# audio.net
KiCad netlist of a schematic drawn in Altium Designer
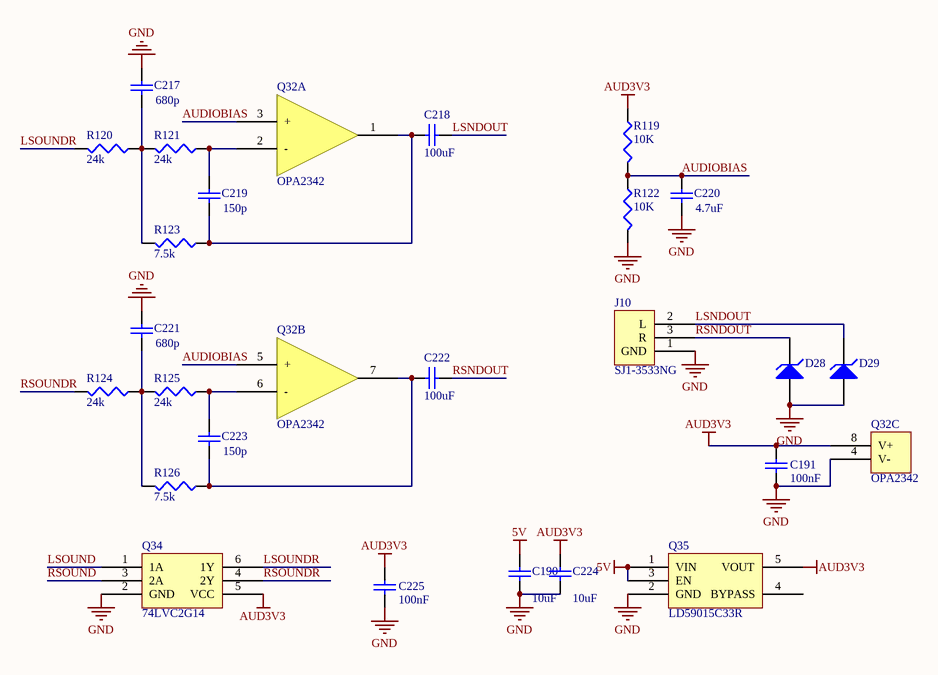
[diagram p0: audio.SchDoc]

(export (version "E")
  (design (tool "Eeschema 10.0.6"))
  (components
    (comp (ref "C190")
      (value "10uF")
      (footprint "CAPC1608X90N")
      (description "Capacitor")
      (fields (field (name "Comment") "GRM188R60G106ME47") (field (name "PUBLISHER") "Altium Limited"))
      (libsource (lib "Miscellaneous Devices") (part "Cap"))
    )
    (comp (ref "C191")
      (value "100nF")
      (footprint "CAPC1005X06L")
      (description "Capacitor")
      (fields (field (name "Comment") "Cap") (field (name "PUBLISHER") "Altium Limited"))
      (libsource (lib "Miscellaneous Devices") (part "Cap"))
    )
    (comp (ref "C217")
      (value "680p")
      (footprint "CAPC1608X90N")
      (description "Capacitor")
      (fields (field (name "PUBLISHER") "Altium Limited"))
      (libsource (lib "Miscellaneous Devices") (part "Cap"))
    )
    (comp (ref "C218")
      (value "100uF")
      (footprint "CAPC3225X220N")
      (description "Capacitor")
      (fields (field (name "Comment") "GRM31CR60J107ME39L") (field (name "PUBLISHER") "Altium Limited"))
      (libsource (lib "Miscellaneous Devices") (part "Cap"))
    )
    (comp (ref "C219")
      (value "150p")
      (footprint "CAPC1608X90N")
      (description "Capacitor")
      (fields (field (name "PUBLISHER") "Altium Limited"))
      (libsource (lib "Miscellaneous Devices") (part "Cap"))
    )
    (comp (ref "C220")
      (value "4.7uF")
      (footprint "CAPC1608X90N")
      (description "Capacitor")
      (fields (field (name "Comment") "GRM188R60J475ME19D") (field (name "PUBLISHER") "Altium Limited"))
      (libsource (lib "Miscellaneous Devices") (part "Cap"))
    )
    (comp (ref "C221")
      (value "680p")
      (footprint "CAPC1608X90N")
      (description "Capacitor")
      (fields (field (name "PUBLISHER") "Altium Limited"))
      (libsource (lib "Miscellaneous Devices") (part "Cap"))
    )
    (comp (ref "C222")
      (value "100uF")
      (footprint "CAPC3225X220N")
      (description "Capacitor")
      (fields (field (name "Comment") "GRM31CR60J107ME39L") (field (name "PUBLISHER") "Altium Limited"))
      (libsource (lib "Miscellaneous Devices") (part "Cap"))
    )
    (comp (ref "C223")
      (value "150p")
      (footprint "CAPC1608X90N")
      (description "Capacitor")
      (fields (field (name "PUBLISHER") "Altium Limited"))
      (libsource (lib "Miscellaneous Devices") (part "Cap"))
    )
    (comp (ref "C224")
      (value "10uF")
      (footprint "CAPC1608X90N")
      (description "Capacitor")
      (fields (field (name "Comment") "GRM188R60G106ME47") (field (name "PUBLISHER") "Altium Limited"))
      (libsource (lib "Miscellaneous Devices") (part "Cap"))
    )
    (comp (ref "C225")
      (value "100nF")
      (footprint "CAPC1005X06L")
      (description "Capacitor")
      (fields (field (name "Comment") "Cap") (field (name "PUBLISHER") "Altium Limited"))
      (libsource (lib "Miscellaneous Devices") (part "Cap"))
    )
    (comp (ref "D28")
      (value "EZAEG2A")
      (footprint "CAPC1005X55N")
      (description "Zener Diode")
      (fields (field (name "PUBLISHER") "Altium Limited"))
      (libsource (lib "Miscellaneous Devices") (part "D Zener"))
    )
    (comp (ref "D29")
      (value "EZAEG2A")
      (footprint "CAPC1005X55N")
      (description "Zener Diode")
      (fields (field (name "PUBLISHER") "Altium Limited"))
      (libsource (lib "Miscellaneous Devices") (part "D Zener"))
    )
    (comp (ref "J10") (value "SJ1-3533NG") (footprint "SJ1-3533NG") (libsource (lib "schlib") (part "AUDIO")))
    (comp (ref "Q32")
      (value "OPA2342")
      (footprint "SOIC127P600X175-8AN")
      (libsource (lib "schlib") (part "OPAMP"))
    )
    (comp (ref "Q34")
      (value "74LVC2G14")
      (footprint "74LVC2G14-SOP6")
      (libsource (lib "schlib") (part "74LVC2G14"))
    )
    (comp (ref "Q35") (value "LD59015C33R") (footprint "SOT23-5") (libsource (lib "schlib") (part "LDO")))
    (comp (ref "R119")
      (value "10K")
      (footprint "J1-0603")
      (description "Resistor")
      (fields (field (name "Comment") "RC1608F103CS") (field (name "PUBLISHER") "Altium Limited"))
      (libsource (lib "Miscellaneous Devices") (part "Res3"))
    )
    (comp (ref "R120")
      (value "24k")
      (footprint "J1-0603")
      (description "Resistor")
      (fields (field (name "Comment") "RC1608F471CS") (field (name "PUBLISHER") "Altium Limited"))
      (libsource (lib "Miscellaneous Devices") (part "Res3"))
    )
    (comp (ref "R121")
      (value "24k")
      (footprint "J1-0603")
      (description "Resistor")
      (fields (field (name "Comment") "RC1608F471CS") (field (name "PUBLISHER") "Altium Limited"))
      (libsource (lib "Miscellaneous Devices") (part "Res3"))
    )
    (comp (ref "R122")
      (value "10K")
      (footprint "J1-0603")
      (description "Resistor")
      (fields (field (name "Comment") "RC1608F103CS") (field (name "PUBLISHER") "Altium Limited"))
      (libsource (lib "Miscellaneous Devices") (part "Res3"))
    )
    (comp (ref "R123")
      (value "7.5k")
      (footprint "J1-0603")
      (description "Resistor")
      (fields (field (name "Comment") "RC1608F471CS") (field (name "PUBLISHER") "Altium Limited"))
      (libsource (lib "Miscellaneous Devices") (part "Res3"))
    )
    (comp (ref "R124")
      (value "24k")
      (footprint "J1-0603")
      (description "Resistor")
      (fields (field (name "Comment") "RC1608F471CS") (field (name "PUBLISHER") "Altium Limited"))
      (libsource (lib "Miscellaneous Devices") (part "Res3"))
    )
    (comp (ref "R125")
      (value "24k")
      (footprint "J1-0603")
      (description "Resistor")
      (fields (field (name "Comment") "RC1608F471CS") (field (name "PUBLISHER") "Altium Limited"))
      (libsource (lib "Miscellaneous Devices") (part "Res3"))
    )
    (comp (ref "R126")
      (value "7.5k")
      (footprint "J1-0603")
      (description "Resistor")
      (fields (field (name "Comment") "RC1608F471CS") (field (name "PUBLISHER") "Altium Limited"))
      (libsource (lib "Miscellaneous Devices") (part "Res3"))
    )
  )
  (nets
    (net (code "1") (name "/AUDIOBIAS") (class "Default")
      (node (ref "C220") (pin "2") (pinfunction "2_2") (pintype "passive"))
      (node (ref "Q32") (pin "3") (pinfunction "+_3") (pintype "passive"))
      (node (ref "Q32") (pin "5") (pinfunction "+_5") (pintype "passive"))
      (node (ref "R119") (pin "2") (pinfunction "2_2") (pintype "passive"))
      (node (ref "R122") (pin "1") (pinfunction "1_1") (pintype "passive"))
    )
    (net (code "2") (name "/LSNDOUT") (class "Default")
      (node (ref "C218") (pin "2") (pinfunction "2_2") (pintype "passive"))
      (node (ref "D29") (pin "2") (pinfunction "K_2") (pintype "passive"))
      (node (ref "J10") (pin "2") (pinfunction "L_2") (pintype "passive"))
    )
    (net (code "3") (name "/LSOUND") (class "Default")
      (node (ref "Q34") (pin "1") (pinfunction "1A_1") (pintype "passive"))
    )
    (net (code "4") (name "/LSOUNDR") (class "Default")
      (node (ref "Q34") (pin "6") (pinfunction "1Y_6") (pintype "passive"))
      (node (ref "R120") (pin "2") (pinfunction "2_2") (pintype "passive"))
    )
    (net (code "5") (name "/RSNDOUT") (class "Default")
      (node (ref "C222") (pin "2") (pinfunction "2_2") (pintype "passive"))
      (node (ref "D28") (pin "2") (pinfunction "K_2") (pintype "passive"))
      (node (ref "J10") (pin "3") (pinfunction "R_3") (pintype "passive"))
    )
    (net (code "6") (name "/RSOUND") (class "Default")
      (node (ref "Q34") (pin "3") (pinfunction "2A_3") (pintype "passive"))
    )
    (net (code "7") (name "/RSOUNDR") (class "Default")
      (node (ref "Q34") (pin "4") (pinfunction "2Y_4") (pintype "passive"))
      (node (ref "R124") (pin "2") (pinfunction "2_2") (pintype "passive"))
    )
    (net (code "8") (name "5V") (class "Default")
      (node (ref "C190") (pin "2") (pinfunction "2_2") (pintype "passive"))
      (node (ref "Q35") (pin "1") (pinfunction "VIN_1") (pintype "passive"))
      (node (ref "Q35") (pin "3") (pinfunction "EN_3") (pintype "passive"))
    )
    (net (code "9") (name "AUD3V3") (class "Default")
      (node (ref "C191") (pin "2") (pinfunction "2_2") (pintype "passive"))
      (node (ref "C224") (pin "2") (pinfunction "2_2") (pintype "passive"))
      (node (ref "C225") (pin "2") (pinfunction "2_2") (pintype "passive"))
      (node (ref "Q32") (pin "8") (pinfunction "V+_8") (pintype "passive"))
      (node (ref "Q34") (pin "5") (pinfunction "VCC_5") (pintype "passive"))
      (node (ref "Q35") (pin "5") (pinfunction "VOUT_5") (pintype "passive"))
      (node (ref "R119") (pin "1") (pinfunction "1_1") (pintype "passive"))
    )
    (net (code "10") (name "GND") (class "Default")
      (node (ref "C190") (pin "1") (pinfunction "1_1") (pintype "passive"))
      (node (ref "C191") (pin "1") (pinfunction "1_1") (pintype "passive"))
      (node (ref "C217") (pin "2") (pinfunction "2_2") (pintype "passive"))
      (node (ref "C220") (pin "1") (pinfunction "1_1") (pintype "passive"))
      (node (ref "C221") (pin "2") (pinfunction "2_2") (pintype "passive"))
      (node (ref "C224") (pin "1") (pinfunction "1_1") (pintype "passive"))
      (node (ref "C225") (pin "1") (pinfunction "1_1") (pintype "passive"))
      (node (ref "D28") (pin "1") (pinfunction "A_1") (pintype "passive"))
      (node (ref "D29") (pin "1") (pinfunction "A_1") (pintype "passive"))
      (node (ref "J10") (pin "1") (pinfunction "GND_1") (pintype "passive"))
      (node (ref "Q32") (pin "4") (pinfunction "V-_4") (pintype "passive"))
      (node (ref "Q34") (pin "2") (pinfunction "GND_2") (pintype "passive"))
      (node (ref "Q35") (pin "2") (pinfunction "GND_2") (pintype "passive"))
      (node (ref "R122") (pin "2") (pinfunction "2_2") (pintype "passive"))
    )
    (net (code "11") (name "Net-(C217-Pad1)") (class "Default")
      (node (ref "C217") (pin "1") (pinfunction "1_1") (pintype "passive"))
      (node (ref "R120") (pin "1") (pinfunction "1_1") (pintype "passive"))
      (node (ref "R121") (pin "2") (pinfunction "2_2") (pintype "passive"))
      (node (ref "R123") (pin "2") (pinfunction "2_2") (pintype "passive"))
    )
    (net (code "12") (name "Net-(C218-Pad1)") (class "Default")
      (node (ref "C218") (pin "1") (pinfunction "1_1") (pintype "passive"))
      (node (ref "C219") (pin "1") (pinfunction "1_1") (pintype "passive"))
      (node (ref "Q32") (pin "1") (pintype "passive"))
      (node (ref "R123") (pin "1") (pinfunction "1_1") (pintype "passive"))
    )
    (net (code "13") (name "Net-(C221-Pad1)") (class "Default")
      (node (ref "C221") (pin "1") (pinfunction "1_1") (pintype "passive"))
      (node (ref "R124") (pin "1") (pinfunction "1_1") (pintype "passive"))
      (node (ref "R125") (pin "2") (pinfunction "2_2") (pintype "passive"))
      (node (ref "R126") (pin "2") (pinfunction "2_2") (pintype "passive"))
    )
    (net (code "14") (name "Net-(C222-Pad1)") (class "Default")
      (node (ref "C222") (pin "1") (pinfunction "1_1") (pintype "passive"))
      (node (ref "C223") (pin "1") (pinfunction "1_1") (pintype "passive"))
      (node (ref "Q32") (pin "7") (pintype "passive"))
      (node (ref "R126") (pin "1") (pinfunction "1_1") (pintype "passive"))
    )
    (net (code "15") (name "Net-(Q32A--)") (class "Default")
      (node (ref "C219") (pin "2") (pinfunction "2_2") (pintype "passive"))
      (node (ref "Q32") (pin "2") (pinfunction "-_2") (pintype "passive"))
      (node (ref "R121") (pin "1") (pinfunction "1_1") (pintype "passive"))
    )
    (net (code "16") (name "Net-(Q32B--)") (class "Default")
      (node (ref "C223") (pin "2") (pinfunction "2_2") (pintype "passive"))
      (node (ref "Q32") (pin "6") (pinfunction "-_6") (pintype "passive"))
      (node (ref "R125") (pin "1") (pinfunction "1_1") (pintype "passive"))
    )
    (net (code "17") (name "unconnected-(Q35-BYPASS-Pad4)") (class "Default")
      (node (ref "Q35") (pin "4") (pinfunction "BYPASS_4") (pintype "passive"))
    )
  )
)
